# SL_LCD_SW_LED_2E.net
KiCad netlist of a schematic drawn in Altium Designer
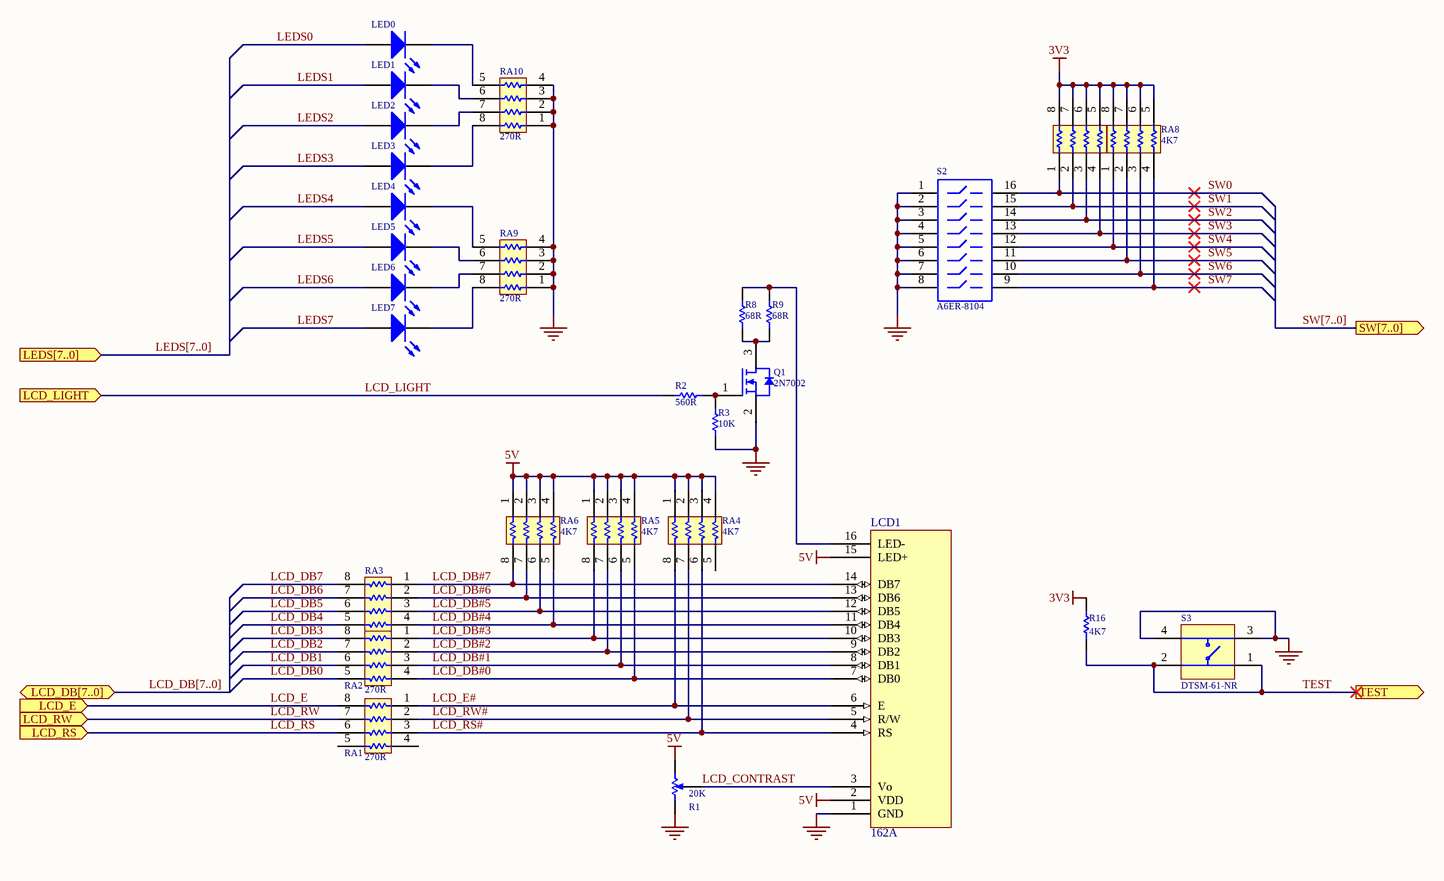
[diagram p0: SL_LCD_SW_LED_2E.SchDoc]

(export (version "E")
  (design (tool "Eeschema 10.0.6"))
  (components
    (comp (ref "LCD1")
      (value "162A")
      (footprint "Spirit_Level_Project:162A")
      (description "16 char * 2 line LCD character display with b/light")
      (libsource (lib "SpiritLevel_2E") (part "162A"))
    )
    (comp (ref "LED0")
      (value "HSMH-C170")
      (footprint "Spirit_Level_Project:SMD _LED")
      (description "Typical RED GaAs SMD LED Agilent make")
      (libsource (lib "SpiritLevel_2E") (part "HSMX-C670"))
    )
    (comp (ref "LED1")
      (value "HSMH-C170")
      (footprint "Spirit_Level_Project:SMD _LED")
      (description "Typical RED GaAs SMD LED Agilent make")
      (libsource (lib "SpiritLevel_2E") (part "HSMX-C670"))
    )
    (comp (ref "LED2")
      (value "HSMH-C170")
      (footprint "Spirit_Level_Project:SMD _LED")
      (description "Typical RED GaAs SMD LED Agilent make")
      (libsource (lib "SpiritLevel_2E") (part "HSMX-C670"))
    )
    (comp (ref "LED3")
      (value "HSMH-C170")
      (footprint "Spirit_Level_Project:SMD _LED")
      (description "Typical RED GaAs SMD LED Agilent make")
      (libsource (lib "SpiritLevel_2E") (part "HSMX-C670"))
    )
    (comp (ref "LED4")
      (value "HSMH-C170")
      (footprint "Spirit_Level_Project:SMD _LED")
      (description "Typical RED GaAs SMD LED Agilent make")
      (libsource (lib "SpiritLevel_2E") (part "HSMX-C670"))
    )
    (comp (ref "LED5")
      (value "HSMH-C170")
      (footprint "Spirit_Level_Project:SMD _LED")
      (description "Typical RED GaAs SMD LED Agilent make")
      (libsource (lib "SpiritLevel_2E") (part "HSMX-C670"))
    )
    (comp (ref "LED6")
      (value "HSMH-C170")
      (footprint "Spirit_Level_Project:SMD _LED")
      (description "Typical RED GaAs SMD LED Agilent make")
      (libsource (lib "SpiritLevel_2E") (part "HSMX-C670"))
    )
    (comp (ref "LED7")
      (value "HSMH-C170")
      (footprint "Spirit_Level_Project:SMD _LED")
      (description "Typical RED GaAs SMD LED Agilent make")
      (libsource (lib "SpiritLevel_2E") (part "HSMX-C670"))
    )
    (comp (ref "Q1")
      (value "2N7002")
      (footprint "Spirit_Level_Project:SO-G3")
      (description "N Channel Mosfet")
      (libsource (lib "SpiritLevel_2E") (part "2N7002"))
    )
    (comp (ref "R1")
      (value "20K")
      (footprint "Spirit_Level_Project:POT4MM-2")
      (description "Square Trimming Potentiometer")
      (libsource (lib "SpiritLevel_2E") (part "RPot SM"))
    )
    (comp (ref "R2")
      (value "560R")
      (footprint "CC2012-0805")
      (description "Resistor")
      (libsource (lib "") (part "RES_1"))
    )
    (comp (ref "R3")
      (value "10K")
      (footprint "CC2012-0805")
      (description "Resistor")
      (libsource (lib "") (part "RES_1"))
    )
    (comp (ref "R8")
      (value "68R")
      (footprint "CC2012-0805")
      (description "Resistor")
      (libsource (lib "SpiritLevel_2E") (part "RES"))
    )
    (comp (ref "R9")
      (value "68R")
      (footprint "CC2012-0805")
      (description "Resistor")
      (libsource (lib "SpiritLevel_2E") (part "RES"))
    )
    (comp (ref "R16")
      (value "4K7")
      (footprint "CC2012-0805")
      (description "Resistor")
      (libsource (lib "") (part "RES_1"))
    )
    (comp (ref "RA1")
      (value "270R")
      (footprint "Spirit_Level_Project:MNR34")
      (description "3216x4 Resistor Array")
      (libsource (lib "") (part "MNR34_3"))
    )
    (comp (ref "RA2")
      (value "270R")
      (footprint "Spirit_Level_Project:MNR34")
      (description "3216x4 Resistor Array")
      (libsource (lib "") (part "MNR34_3"))
    )
    (comp (ref "RA3")
      (value "270R")
      (footprint "Spirit_Level_Project:MNR34")
      (description "3216x4 Resistor Array")
      (libsource (lib "") (part "MNR34_3"))
    )
    (comp (ref "RA4")
      (value "4K7")
      (footprint "Spirit_Level_Project:MNR34T")
      (description "3216x4 Resistor Array")
      (libsource (lib "SpiritLevel_2E") (part "MNR34"))
    )
    (comp (ref "RA5")
      (value "4K7")
      (footprint "Spirit_Level_Project:MNR34T")
      (description "3216x4 Resistor Array")
      (libsource (lib "SpiritLevel_2E") (part "MNR34"))
    )
    (comp (ref "RA6")
      (value "4K7")
      (footprint "Spirit_Level_Project:MNR34T")
      (description "3216x4 Resistor Array")
      (libsource (lib "SpiritLevel_2E") (part "MNR34"))
    )
    (comp (ref "RA7")
      (value "4K7")
      (footprint "Spirit_Level_Project:MNR34T")
      (description "3216x4 Resistor Array")
      (libsource (lib "") (part "MNR34_1"))
    )
    (comp (ref "RA8")
      (value "4K7")
      (footprint "Spirit_Level_Project:MNR34T")
      (description "3216x4 Resistor Array")
      (libsource (lib "") (part "MNR34_1"))
    )
    (comp (ref "RA9")
      (value "270R")
      (footprint "Spirit_Level_Project:MNR34T")
      (description "3216x4 Resistor Array")
      (libsource (lib "") (part "MNR34_2"))
    )
    (comp (ref "RA10")
      (value "270R")
      (footprint "Spirit_Level_Project:MNR34T")
      (description "3216x4 Resistor Array")
      (libsource (lib "") (part "MNR34_2"))
    )
    (comp (ref "S2")
      (value "A6ER-8104")
      (footprint "Spirit_Level_Project:DIP-16-KEY")
      (description "DIP Switch Side actuator long liver Piano Key")
      (libsource (lib "SpiritLevel_2E") (part "A6ER-8104"))
    )
    (comp (ref "S3")
      (value "DTSM-61-NR")
      (footprint "Spirit_Level_Project:B3FS_SWITCH")
      (description "SPNA SMD Keyboard Switch")
      (libsource (lib "SpiritLevel_2E") (part "B3FS"))
    )
  )
  (nets
    (net (code "1") (name "/LCD_CONTRAST") (class "Default")
      (node (ref "LCD1") (pin "3") (pinfunction "Vo_3") (pintype "tri_state"))
      (node (ref "R1") (pin "W") (pintype "passive"))
    )
    (net (code "2") (name "/LCD_DB#0") (class "Default")
      (node (ref "LCD1") (pin "7") (pinfunction "DB0_7") (pintype "bidirectional"))
      (node (ref "RA2") (pin "4") (pintype "passive"))
      (node (ref "RA5") (pin "5") (pintype "passive"))
    )
    (net (code "3") (name "/LCD_DB#1") (class "Default")
      (node (ref "LCD1") (pin "8") (pinfunction "DB1_8") (pintype "bidirectional"))
      (node (ref "RA2") (pin "3") (pintype "passive"))
      (node (ref "RA5") (pin "6") (pintype "passive"))
    )
    (net (code "4") (name "/LCD_DB#2") (class "Default")
      (node (ref "LCD1") (pin "9") (pinfunction "DB2_9") (pintype "bidirectional"))
      (node (ref "RA2") (pin "2") (pintype "passive"))
      (node (ref "RA5") (pin "7") (pintype "passive"))
    )
    (net (code "5") (name "/LCD_DB#3") (class "Default")
      (node (ref "LCD1") (pin "10") (pinfunction "DB3_10") (pintype "bidirectional"))
      (node (ref "RA2") (pin "1") (pintype "passive"))
      (node (ref "RA5") (pin "8") (pintype "passive"))
    )
    (net (code "6") (name "/LCD_DB#4") (class "Default")
      (node (ref "LCD1") (pin "11") (pinfunction "DB4_11") (pintype "bidirectional"))
      (node (ref "RA3") (pin "4") (pintype "passive"))
      (node (ref "RA6") (pin "5") (pintype "passive"))
    )
    (net (code "7") (name "/LCD_DB#5") (class "Default")
      (node (ref "LCD1") (pin "12") (pinfunction "DB5_12") (pintype "bidirectional"))
      (node (ref "RA3") (pin "3") (pintype "passive"))
      (node (ref "RA6") (pin "6") (pintype "passive"))
    )
    (net (code "8") (name "/LCD_DB#6") (class "Default")
      (node (ref "LCD1") (pin "13") (pinfunction "DB6_13") (pintype "bidirectional"))
      (node (ref "RA3") (pin "2") (pintype "passive"))
      (node (ref "RA6") (pin "7") (pintype "passive"))
    )
    (net (code "9") (name "/LCD_DB#7") (class "Default")
      (node (ref "LCD1") (pin "14") (pinfunction "DB7_14") (pintype "bidirectional"))
      (node (ref "RA3") (pin "1") (pintype "passive"))
      (node (ref "RA6") (pin "8") (pintype "passive"))
    )
    (net (code "10") (name "/LCD_DB0") (class "Default") (node (ref "RA2") (pin "5") (pintype "passive")))
    (net (code "11") (name "/LCD_DB1") (class "Default") (node (ref "RA2") (pin "6") (pintype "passive")))
    (net (code "12") (name "/LCD_DB2") (class "Default") (node (ref "RA2") (pin "7") (pintype "passive")))
    (net (code "13") (name "/LCD_DB3") (class "Default") (node (ref "RA2") (pin "8") (pintype "passive")))
    (net (code "14") (name "/LCD_DB4") (class "Default") (node (ref "RA3") (pin "5") (pintype "passive")))
    (net (code "15") (name "/LCD_DB5") (class "Default") (node (ref "RA3") (pin "6") (pintype "passive")))
    (net (code "16") (name "/LCD_DB6") (class "Default") (node (ref "RA3") (pin "7") (pintype "passive")))
    (net (code "17") (name "/LCD_DB7") (class "Default") (node (ref "RA3") (pin "8") (pintype "passive")))
    (net (code "19") (name "/LCD_E") (class "Default") (node (ref "RA1") (pin "8") (pintype "passive")))
    (net (code "20") (name "/LCD_E#") (class "Default")
      (node (ref "LCD1") (pin "6") (pinfunction "E_6") (pintype "input"))
      (node (ref "RA1") (pin "1") (pintype "passive"))
      (node (ref "RA4") (pin "8") (pintype "passive"))
    )
    (net (code "21") (name "/LCD_LIGHT") (class "Default")
      (node (ref "R2") (pin "1") (pinfunction "1_1") (pintype "passive"))
    )
    (net (code "22") (name "/LCD_RS") (class "Default") (node (ref "RA1") (pin "6") (pintype "passive")))
    (net (code "23") (name "/LCD_RS#") (class "Default")
      (node (ref "LCD1") (pin "4") (pinfunction "RS_4") (pintype "input"))
      (node (ref "RA1") (pin "3") (pintype "passive"))
      (node (ref "RA4") (pin "6") (pintype "passive"))
    )
    (net (code "24") (name "/LCD_RW") (class "Default") (node (ref "RA1") (pin "7") (pintype "passive")))
    (net (code "25") (name "/LCD_RW#") (class "Default")
      (node (ref "LCD1") (pin "5") (pinfunction "R/W_5") (pintype "input"))
      (node (ref "RA1") (pin "2") (pintype "passive"))
      (node (ref "RA4") (pin "7") (pintype "passive"))
    )
    (net (code "26") (name "/LEDS0") (class "Default")
      (node (ref "LED0") (pin "1") (pinfunction "A_1") (pintype "passive"))
    )
    (net (code "27") (name "/LEDS1") (class "Default")
      (node (ref "LED1") (pin "1") (pinfunction "A_1") (pintype "passive"))
    )
    (net (code "28") (name "/LEDS2") (class "Default")
      (node (ref "LED2") (pin "1") (pinfunction "A_1") (pintype "passive"))
    )
    (net (code "29") (name "/LEDS3") (class "Default")
      (node (ref "LED3") (pin "1") (pinfunction "A_1") (pintype "passive"))
    )
    (net (code "30") (name "/LEDS4") (class "Default")
      (node (ref "LED4") (pin "1") (pinfunction "A_1") (pintype "passive"))
    )
    (net (code "31") (name "/LEDS5") (class "Default")
      (node (ref "LED5") (pin "1") (pinfunction "A_1") (pintype "passive"))
    )
    (net (code "32") (name "/LEDS6") (class "Default")
      (node (ref "LED6") (pin "1") (pinfunction "A_1") (pintype "passive"))
    )
    (net (code "33") (name "/LEDS7") (class "Default")
      (node (ref "LED7") (pin "1") (pinfunction "A_1") (pintype "passive"))
    )
    (net (code "35") (name "/SW0") (class "Default")
      (node (ref "RA7") (pin "1") (pintype "passive"))
      (node (ref "S2") (pin "16") (pinfunction "16_16") (pintype "passive"))
    )
    (net (code "36") (name "/SW1") (class "Default")
      (node (ref "RA7") (pin "2") (pintype "passive"))
      (node (ref "S2") (pin "15") (pinfunction "15_15") (pintype "passive"))
    )
    (net (code "37") (name "/SW2") (class "Default")
      (node (ref "RA7") (pin "3") (pintype "passive"))
      (node (ref "S2") (pin "14") (pinfunction "14_14") (pintype "passive"))
    )
    (net (code "38") (name "/SW3") (class "Default")
      (node (ref "RA7") (pin "4") (pintype "passive"))
      (node (ref "S2") (pin "13") (pinfunction "13_13") (pintype "passive"))
    )
    (net (code "39") (name "/SW4") (class "Default")
      (node (ref "RA8") (pin "1") (pintype "passive"))
      (node (ref "S2") (pin "12") (pinfunction "12_12") (pintype "passive"))
    )
    (net (code "40") (name "/SW5") (class "Default")
      (node (ref "RA8") (pin "2") (pintype "passive"))
      (node (ref "S2") (pin "11") (pinfunction "11_11") (pintype "passive"))
    )
    (net (code "41") (name "/SW6") (class "Default")
      (node (ref "RA8") (pin "3") (pintype "passive"))
      (node (ref "S2") (pin "10") (pinfunction "10_10") (pintype "passive"))
    )
    (net (code "42") (name "/SW7") (class "Default")
      (node (ref "RA8") (pin "4") (pintype "passive"))
      (node (ref "S2") (pin "9") (pinfunction "9_9") (pintype "passive"))
    )
    (net (code "44") (name "/TEST") (class "Default")
      (node (ref "R16") (pin "2") (pinfunction "2_2") (pintype "passive"))
      (node (ref "S3") (pin "1") (pinfunction "1_1") (pintype "passive"))
      (node (ref "S3") (pin "2") (pinfunction "2_2") (pintype "passive"))
    )
    (net (code "45") (name "3V3") (class "Default")
      (node (ref "R16") (pin "1") (pinfunction "1_1") (pintype "passive"))
      (node (ref "RA7") (pin "5") (pintype "passive"))
      (node (ref "RA7") (pin "6") (pintype "passive"))
      (node (ref "RA7") (pin "7") (pintype "passive"))
      (node (ref "RA7") (pin "8") (pintype "passive"))
      (node (ref "RA8") (pin "5") (pintype "passive"))
      (node (ref "RA8") (pin "6") (pintype "passive"))
      (node (ref "RA8") (pin "7") (pintype "passive"))
      (node (ref "RA8") (pin "8") (pintype "passive"))
    )
    (net (code "46") (name "5V") (class "Default")
      (node (ref "LCD1") (pin "15") (pinfunction "LED+_15") (pintype "power_in"))
      (node (ref "LCD1") (pin "2") (pinfunction "VDD_2") (pintype "power_in"))
      (node (ref "R1") (pin "CW") (pinfunction "+_CW") (pintype "passive"))
      (node (ref "RA4") (pin "1") (pintype "passive"))
      (node (ref "RA4") (pin "2") (pintype "passive"))
      (node (ref "RA4") (pin "3") (pintype "passive"))
      (node (ref "RA4") (pin "4") (pintype "passive"))
      (node (ref "RA5") (pin "1") (pintype "passive"))
      (node (ref "RA5") (pin "2") (pintype "passive"))
      (node (ref "RA5") (pin "3") (pintype "passive"))
      (node (ref "RA5") (pin "4") (pintype "passive"))
      (node (ref "RA6") (pin "1") (pintype "passive"))
      (node (ref "RA6") (pin "2") (pintype "passive"))
      (node (ref "RA6") (pin "3") (pintype "passive"))
      (node (ref "RA6") (pin "4") (pintype "passive"))
    )
    (net (code "47") (name "GND") (class "Default")
      (node (ref "LCD1") (pin "1") (pinfunction "GND_1") (pintype "power_in"))
      (node (ref "Q1") (pin "2") (pintype "passive"))
      (node (ref "R1") (pin "CCW") (pinfunction "-_CCW") (pintype "passive"))
      (node (ref "R3") (pin "1") (pinfunction "1_1") (pintype "passive"))
      (node (ref "RA10") (pin "1") (pintype "passive"))
      (node (ref "RA10") (pin "2") (pintype "passive"))
      (node (ref "RA10") (pin "3") (pintype "passive"))
      (node (ref "RA10") (pin "4") (pintype "passive"))
      (node (ref "RA9") (pin "1") (pintype "passive"))
      (node (ref "RA9") (pin "2") (pintype "passive"))
      (node (ref "RA9") (pin "3") (pintype "passive"))
      (node (ref "RA9") (pin "4") (pintype "passive"))
      (node (ref "S2") (pin "1") (pinfunction "1_1") (pintype "passive"))
      (node (ref "S2") (pin "2") (pinfunction "2_2") (pintype "passive"))
      (node (ref "S2") (pin "3") (pinfunction "3_3") (pintype "passive"))
      (node (ref "S2") (pin "4") (pinfunction "4_4") (pintype "passive"))
      (node (ref "S2") (pin "5") (pinfunction "5_5") (pintype "passive"))
      (node (ref "S2") (pin "6") (pinfunction "6_6") (pintype "passive"))
      (node (ref "S2") (pin "7") (pinfunction "7_7") (pintype "passive"))
      (node (ref "S2") (pin "8") (pinfunction "8_8") (pintype "passive"))
      (node (ref "S3") (pin "3") (pinfunction "3_3") (pintype "passive"))
      (node (ref "S3") (pin "4") (pinfunction "4_4") (pintype "passive"))
    )
    (net (code "48") (name "Net-(LCD1-LED-)") (class "Default")
      (node (ref "LCD1") (pin "16") (pinfunction "LED-_16") (pintype "power_in"))
      (node (ref "R8") (pin "1") (pinfunction "1_1") (pintype "passive"))
      (node (ref "R9") (pin "1") (pinfunction "1_1") (pintype "passive"))
    )
    (net (code "49") (name "Net-(LED0-K)") (class "Default")
      (node (ref "LED0") (pin "2") (pinfunction "K_2") (pintype "passive"))
      (node (ref "RA10") (pin "5") (pintype "passive"))
    )
    (net (code "50") (name "Net-(LED1-K)") (class "Default")
      (node (ref "LED1") (pin "2") (pinfunction "K_2") (pintype "passive"))
      (node (ref "RA10") (pin "6") (pintype "passive"))
    )
    (net (code "51") (name "Net-(LED2-K)") (class "Default")
      (node (ref "LED2") (pin "2") (pinfunction "K_2") (pintype "passive"))
      (node (ref "RA10") (pin "7") (pintype "passive"))
    )
    (net (code "52") (name "Net-(LED3-K)") (class "Default")
      (node (ref "LED3") (pin "2") (pinfunction "K_2") (pintype "passive"))
      (node (ref "RA10") (pin "8") (pintype "passive"))
    )
    (net (code "53") (name "Net-(LED4-K)") (class "Default")
      (node (ref "LED4") (pin "2") (pinfunction "K_2") (pintype "passive"))
      (node (ref "RA9") (pin "5") (pintype "passive"))
    )
    (net (code "54") (name "Net-(LED5-K)") (class "Default")
      (node (ref "LED5") (pin "2") (pinfunction "K_2") (pintype "passive"))
      (node (ref "RA9") (pin "6") (pintype "passive"))
    )
    (net (code "55") (name "Net-(LED6-K)") (class "Default")
      (node (ref "LED6") (pin "2") (pinfunction "K_2") (pintype "passive"))
      (node (ref "RA9") (pin "7") (pintype "passive"))
    )
    (net (code "56") (name "Net-(LED7-K)") (class "Default")
      (node (ref "LED7") (pin "2") (pinfunction "K_2") (pintype "passive"))
      (node (ref "RA9") (pin "8") (pintype "passive"))
    )
    (net (code "57") (name "Net-(Q1-Pad1)") (class "Default")
      (node (ref "Q1") (pin "1") (pintype "passive"))
      (node (ref "R2") (pin "2") (pinfunction "2_2") (pintype "passive"))
      (node (ref "R3") (pin "2") (pinfunction "2_2") (pintype "passive"))
    )
    (net (code "58") (name "Net-(Q1-Pad3)") (class "Default")
      (node (ref "Q1") (pin "3") (pintype "passive"))
      (node (ref "R8") (pin "2") (pinfunction "2_2") (pintype "passive"))
      (node (ref "R9") (pin "2") (pinfunction "2_2") (pintype "passive"))
    )
    (net (code "59") (name "unconnected-(RA1-Pad4)") (class "Default")
      (node (ref "RA1") (pin "4") (pintype "passive"))
    )
    (net (code "60") (name "unconnected-(RA1-Pad5)") (class "Default")
      (node (ref "RA1") (pin "5") (pintype "passive"))
    )
    (net (code "61") (name "unconnected-(RA4-Pad5)") (class "Default")
      (node (ref "RA4") (pin "5") (pintype "passive"))
    )
  )
)
